# powerSupply.net
KiCad netlist of a schematic drawn in EAGLE
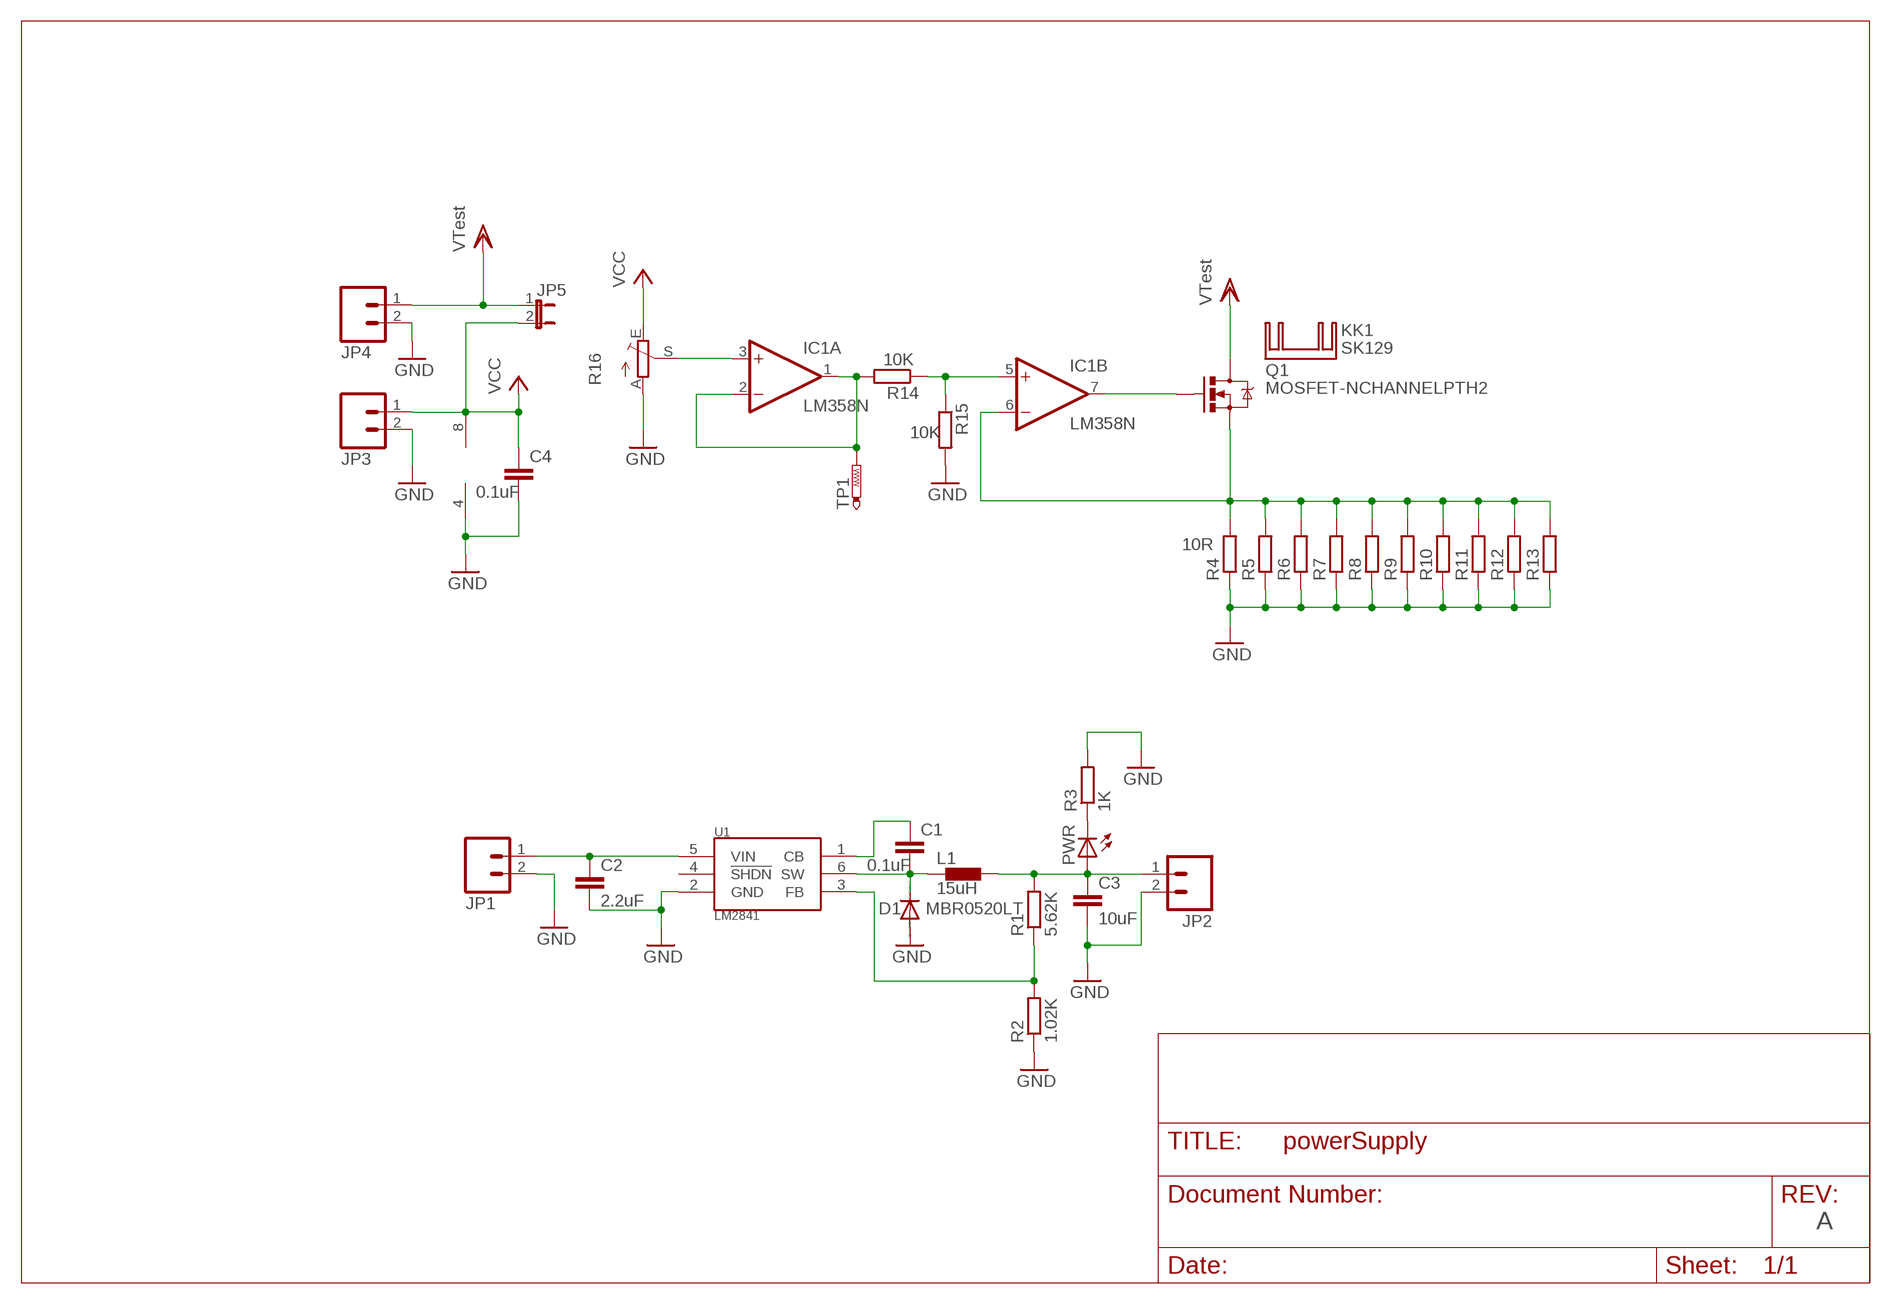
[diagram p0: schematic, sheet 1]

(export (version "E")
  (design (tool "Eeschema 10.0.6"))
  (components
    (comp (ref "C1")
      (value "0.1uF")
      (footprint "eagle-import:C0805")
      (libsource (lib "eagle-import") (part "C-EUC0805"))
    )
    (comp (ref "C2")
      (value "2.2uF")
      (footprint "eagle-import:C1206")
      (libsource (lib "eagle-import") (part "C-EUC1206"))
    )
    (comp (ref "C3")
      (value "10uF")
      (footprint "eagle-import:C1206")
      (libsource (lib "eagle-import") (part "C-EUC1206"))
    )
    (comp (ref "C4")
      (value "0.1uF")
      (footprint "eagle-import:C0805")
      (libsource (lib "eagle-import") (part "C-EUC0805"))
    )
    (comp (ref "D1")
      (value "MBR0520LT")
      (footprint "eagle-import:SOD123")
      (libsource (lib "eagle-import") (part "MBR0520LT"))
    )
    (comp (ref "IC1")
      (value "LM358N")
      (footprint "eagle-import:DIL08")
      (libsource (lib "eagle-import") (part "LM358N"))
    )
    (comp (ref "JP1")
      (value "M02PTH")
      (footprint "eagle-import:1X02")
      (libsource (lib "eagle-import") (part "M02PTH"))
    )
    (comp (ref "JP2")
      (value "M02PTH")
      (footprint "eagle-import:1X02")
      (libsource (lib "eagle-import") (part "M02PTH"))
    )
    (comp (ref "JP3")
      (value "M02PTH")
      (footprint "eagle-import:1X02")
      (libsource (lib "eagle-import") (part "M02PTH"))
    )
    (comp (ref "JP4")
      (value "M02PTH")
      (footprint "eagle-import:1X02")
      (libsource (lib "eagle-import") (part "M02PTH"))
    )
    (comp (ref "JP5")
      (value "JUMPER-2PTH")
      (footprint "eagle-import:1X02")
      (libsource (lib "eagle-import") (part "JUMPER-2PTH"))
    )
    (comp (ref "KK1")
      (value "SK129")
      (footprint "eagle-import:SK129-HOLE")
      (libsource (lib "eagle-import") (part "SK129"))
    )
    (comp (ref "L1")
      (value "15uH")
      (footprint "eagle-import:LQH")
      (libsource (lib "eagle-import") (part "LQHXXSNLQH55DN"))
    )
    (comp (ref "PWR")
      (value "LEDCHIPLED_0805")
      (footprint "eagle-import:CHIPLED_0805")
      (libsource (lib "eagle-import") (part "LEDCHIPLED_0805"))
    )
    (comp (ref "Q1")
      (value "MOSFET-NCHANNELPTH2")
      (footprint "eagle-import:TO220V")
      (libsource (lib "eagle-import") (part "MOSFET-NCHANNELPTH2"))
    )
    (comp (ref "R1")
      (value "5.62K")
      (footprint "eagle-import:M0805")
      (libsource (lib "eagle-import") (part "R-EU_M0805"))
    )
    (comp (ref "R2")
      (value "1.02K")
      (footprint "eagle-import:M0805")
      (libsource (lib "eagle-import") (part "R-EU_M0805"))
    )
    (comp (ref "R3")
      (value "1K")
      (footprint "eagle-import:M0805")
      (libsource (lib "eagle-import") (part "R-EU_M0805"))
    )
    (comp (ref "R4")
      (value "10R")
      (footprint "eagle-import:M0805")
      (libsource (lib "eagle-import") (part "resistor_R-EU_M0805"))
    )
    (comp (ref "R5")
      (value "R-EU_M0805")
      (footprint "eagle-import:M0805")
      (libsource (lib "eagle-import") (part "resistor_R-EU_M0805"))
    )
    (comp (ref "R6")
      (value "R-EU_M0805")
      (footprint "eagle-import:M0805")
      (libsource (lib "eagle-import") (part "resistor_R-EU_M0805"))
    )
    (comp (ref "R7")
      (value "R-EU_M0805")
      (footprint "eagle-import:M0805")
      (libsource (lib "eagle-import") (part "resistor_R-EU_M0805"))
    )
    (comp (ref "R8")
      (value "R-EU_M0805")
      (footprint "eagle-import:M0805")
      (libsource (lib "eagle-import") (part "resistor_R-EU_M0805"))
    )
    (comp (ref "R9")
      (value "R-EU_M0805")
      (footprint "eagle-import:M0805")
      (libsource (lib "eagle-import") (part "resistor_R-EU_M0805"))
    )
    (comp (ref "R10")
      (value "R-EU_M0805")
      (footprint "eagle-import:M0805")
      (libsource (lib "eagle-import") (part "resistor_R-EU_M0805"))
    )
    (comp (ref "R11")
      (value "R-EU_M0805")
      (footprint "eagle-import:M0805")
      (libsource (lib "eagle-import") (part "resistor_R-EU_M0805"))
    )
    (comp (ref "R12")
      (value "R-EU_M0805")
      (footprint "eagle-import:M0805")
      (libsource (lib "eagle-import") (part "resistor_R-EU_M0805"))
    )
    (comp (ref "R13")
      (value "R-EU_M0805")
      (footprint "eagle-import:M0805")
      (libsource (lib "eagle-import") (part "resistor_R-EU_M0805"))
    )
    (comp (ref "R14")
      (value "10K")
      (footprint "eagle-import:M0805")
      (libsource (lib "eagle-import") (part "resistor_R-EU_M0805"))
    )
    (comp (ref "R15")
      (value "10K")
      (footprint "eagle-import:M0805")
      (libsource (lib "eagle-import") (part "resistor_R-EU_M0805"))
    )
    (comp (ref "R16")
      (value "TRIM_EU-B64Y")
      (footprint "eagle-import:B64Y")
      (libsource (lib "eagle-import") (part "TRIM_EU-B64Y"))
    )
    (comp (ref "TP1")
      (value "PTR1TP20R")
      (footprint "eagle-import:TP20R")
      (libsource (lib "eagle-import") (part "PTR1TP20R"))
    )
    (comp (ref "U1")
      (value "LM2841")
      (footprint "eagle-import:TSOT6")
      (libsource (lib "eagle-import") (part "LM2841"))
    )
  )
  (nets
    (net (code "1") (name "GND") (class "Default")
      (node (ref "C2") (pin "2") (pinfunction "2_2") (pintype "passive"))
      (node (ref "C3") (pin "2") (pinfunction "2_2") (pintype "passive"))
      (node (ref "C4") (pin "2") (pinfunction "2_2") (pintype "passive"))
      (node (ref "D1") (pin "A") (pinfunction "A_A") (pintype "passive"))
      (node (ref "IC1") (pin "4") (pinfunction "V-_4") (pintype "power_in"))
      (node (ref "JP1") (pin "2") (pinfunction "2_2") (pintype "passive"))
      (node (ref "JP2") (pin "2") (pinfunction "2_2") (pintype "passive"))
      (node (ref "JP3") (pin "2") (pinfunction "2_2") (pintype "passive"))
      (node (ref "JP4") (pin "2") (pinfunction "2_2") (pintype "passive"))
      (node (ref "R10") (pin "1") (pinfunction "1_1") (pintype "passive"))
      (node (ref "R11") (pin "1") (pinfunction "1_1") (pintype "passive"))
      (node (ref "R12") (pin "1") (pinfunction "1_1") (pintype "passive"))
      (node (ref "R13") (pin "1") (pinfunction "1_1") (pintype "passive"))
      (node (ref "R15") (pin "2") (pinfunction "2_2") (pintype "passive"))
      (node (ref "R16") (pin "A") (pinfunction "A_A") (pintype "passive"))
      (node (ref "R2") (pin "1") (pinfunction "1_1") (pintype "passive"))
      (node (ref "R3") (pin "2") (pinfunction "2_2") (pintype "passive"))
      (node (ref "R4") (pin "1") (pinfunction "1_1") (pintype "passive"))
      (node (ref "R5") (pin "1") (pinfunction "1_1") (pintype "passive"))
      (node (ref "R6") (pin "1") (pinfunction "1_1") (pintype "passive"))
      (node (ref "R7") (pin "1") (pinfunction "1_1") (pintype "passive"))
      (node (ref "R8") (pin "1") (pinfunction "1_1") (pintype "passive"))
      (node (ref "R9") (pin "1") (pinfunction "1_1") (pintype "passive"))
      (node (ref "U1") (pin "2") (pinfunction "GND_2") (pintype "power_in"))
    )
    (net (code "2") (name "Net-(C3-Pad1)") (class "Default")
      (node (ref "C3") (pin "1") (pinfunction "1_1") (pintype "passive"))
      (node (ref "JP2") (pin "1") (pinfunction "1_1") (pintype "passive"))
      (node (ref "L1") (pin "2") (pinfunction "2_2") (pintype "passive"))
      (node (ref "PWR") (pin "A") (pinfunction "A_A") (pintype "passive"))
      (node (ref "R1") (pin "2") (pinfunction "2_2") (pintype "passive"))
    )
    (net (code "3") (name "Net-(IC1A-+IN)") (class "Default")
      (node (ref "IC1") (pin "3") (pinfunction "+IN_3") (pintype "input"))
      (node (ref "R16") (pin "S") (pinfunction "S_S") (pintype "passive"))
    )
    (net (code "4") (name "Net-(IC1A--IN)") (class "Default")
      (node (ref "IC1") (pin "1") (pinfunction "OUT_1") (pintype "output"))
      (node (ref "IC1") (pin "2") (pinfunction "-IN_2") (pintype "input"))
      (node (ref "R14") (pin "2") (pinfunction "2_2") (pintype "passive"))
      (node (ref "TP1") (pin "TP") (pinfunction "TP_TP") (pintype "input"))
    )
    (net (code "5") (name "Net-(IC1B-+IN)") (class "Default")
      (node (ref "IC1") (pin "5") (pinfunction "+IN_5") (pintype "input"))
      (node (ref "R14") (pin "1") (pinfunction "1_1") (pintype "passive"))
      (node (ref "R15") (pin "1") (pinfunction "1_1") (pintype "passive"))
    )
    (net (code "6") (name "Net-(IC1B--IN)") (class "Default")
      (node (ref "IC1") (pin "6") (pinfunction "-IN_6") (pintype "input"))
      (node (ref "Q1") (pin "3") (pinfunction "S_3") (pintype "passive"))
      (node (ref "R10") (pin "2") (pinfunction "2_2") (pintype "passive"))
      (node (ref "R11") (pin "2") (pinfunction "2_2") (pintype "passive"))
      (node (ref "R12") (pin "2") (pinfunction "2_2") (pintype "passive"))
      (node (ref "R13") (pin "2") (pinfunction "2_2") (pintype "passive"))
      (node (ref "R4") (pin "2") (pinfunction "2_2") (pintype "passive"))
      (node (ref "R5") (pin "2") (pinfunction "2_2") (pintype "passive"))
      (node (ref "R6") (pin "2") (pinfunction "2_2") (pintype "passive"))
      (node (ref "R7") (pin "2") (pinfunction "2_2") (pintype "passive"))
      (node (ref "R8") (pin "2") (pinfunction "2_2") (pintype "passive"))
      (node (ref "R9") (pin "2") (pinfunction "2_2") (pintype "passive"))
    )
    (net (code "7") (name "Net-(IC1B-OUT)") (class "Default")
      (node (ref "IC1") (pin "7") (pinfunction "OUT_7") (pintype "output"))
      (node (ref "Q1") (pin "1") (pinfunction "G_1") (pintype "passive"))
    )
    (net (code "8") (name "Net-(PWR-PadC)") (class "Default")
      (node (ref "PWR") (pin "C") (pinfunction "C_C") (pintype "passive"))
      (node (ref "R3") (pin "1") (pinfunction "1_1") (pintype "passive"))
    )
    (net (code "9") (name "Net-(U1-CB)") (class "Default")
      (node (ref "C1") (pin "1") (pinfunction "1_1") (pintype "passive"))
      (node (ref "U1") (pin "1") (pinfunction "CB_1") (pintype "passive"))
    )
    (net (code "10") (name "Net-(U1-FB)") (class "Default")
      (node (ref "R1") (pin "1") (pinfunction "1_1") (pintype "passive"))
      (node (ref "R2") (pin "2") (pinfunction "2_2") (pintype "passive"))
      (node (ref "U1") (pin "3") (pinfunction "FB_3") (pintype "passive"))
    )
    (net (code "11") (name "Net-(U1-SW)") (class "Default")
      (node (ref "C1") (pin "2") (pinfunction "2_2") (pintype "passive"))
      (node (ref "D1") (pin "C") (pinfunction "C_C") (pintype "passive"))
      (node (ref "L1") (pin "1") (pinfunction "1_1") (pintype "passive"))
      (node (ref "U1") (pin "6") (pinfunction "SW_6") (pintype "passive"))
    )
    (net (code "12") (name "Net-(U1-VIN)") (class "Default")
      (node (ref "C2") (pin "1") (pinfunction "1_1") (pintype "passive"))
      (node (ref "JP1") (pin "1") (pinfunction "1_1") (pintype "passive"))
      (node (ref "U1") (pin "5") (pinfunction "VIN_5") (pintype "power_in"))
    )
    (net (code "13") (name "VCC") (class "Default")
      (node (ref "C4") (pin "1") (pinfunction "1_1") (pintype "passive"))
      (node (ref "IC1") (pin "8") (pinfunction "V+_8") (pintype "power_in"))
      (node (ref "JP3") (pin "1") (pinfunction "1_1") (pintype "passive"))
      (node (ref "JP5") (pin "2") (pinfunction "2_2") (pintype "passive"))
      (node (ref "R16") (pin "E") (pinfunction "E_E") (pintype "passive"))
    )
    (net (code "14") (name "VTest") (class "Default")
      (node (ref "JP4") (pin "1") (pinfunction "1_1") (pintype "passive"))
      (node (ref "JP5") (pin "1") (pinfunction "1_1") (pintype "passive"))
      (node (ref "Q1") (pin "2") (pinfunction "D_2") (pintype "passive"))
    )
    (net (code "15") (name "unconnected-(U1-~{SHDN}-Pad4)") (class "Default")
      (node (ref "U1") (pin "4") (pinfunction "~{SHDN}_4") (pintype "input"))
    )
  )
)
